# CAN.net
KiCad netlist of a schematic drawn in Altium Designer
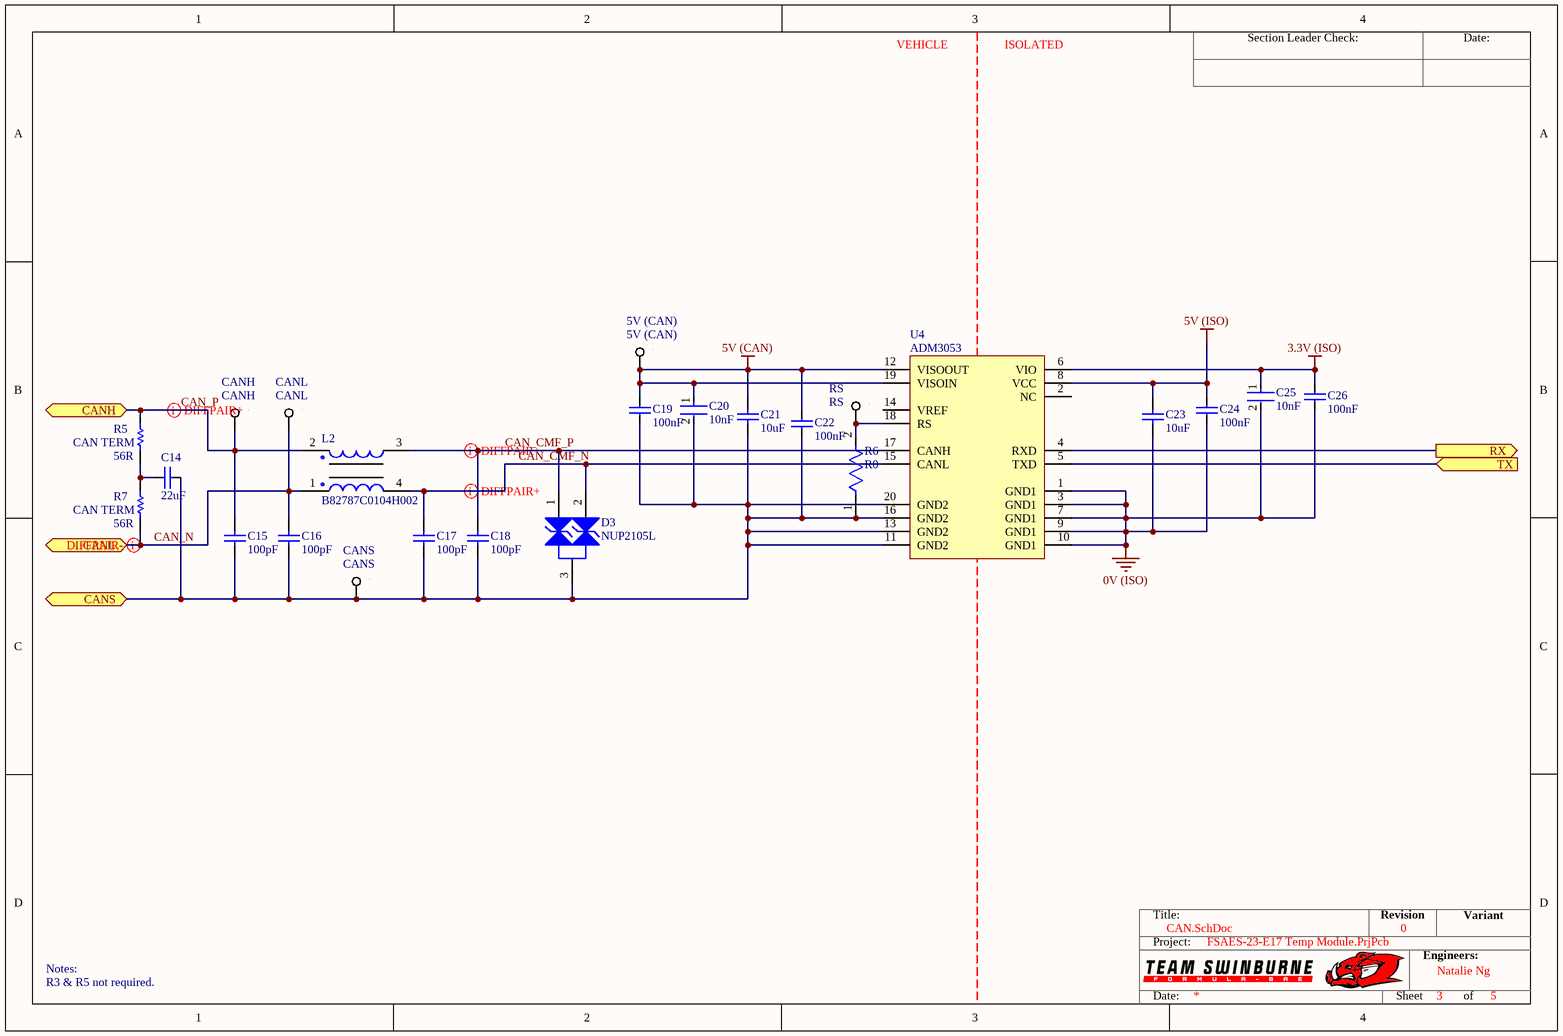
[diagram p0: CAN.SchDoc]

(export (version "E")
  (design (tool "Eeschema 10.0.6"))
  (components
    (comp (ref "5V (CAN)")
      (value "5V (CAN)")
      (footprint "SMD Test Point 1mm")
      (fields (field (name "PART NUMBER") "SMD Test Point Small") (field (name "CONTACT") "NA"))
      (libsource (lib "ts_20-standard-connectors") (part "Test Point Small"))
    )
    (comp (ref "C14")
      (value "22uF")
      (footprint "C0805C226M9PAC7210-Footprint-1")
      (description "Cap Ceramic 22uF 6.3V X5R 20% Pad SMD 0805 85C T/R")
      (fields (field (name "TOLERANCE") "20%"))
      (libsource (lib "Team Swinburne") (part "C0805C226M9PAC7210-Symbol-1"))
    )
    (comp (ref "C15")
      (value "100pF")
      (footprint "CAPC2013X70X45NL15T25")
      (description "Cap Ceramic 100pF 50V C0G 5% Pad SMD 0805 125C Automotive T/R")
      (fields (field (name "TOLERANCE") "5%"))
      (libsource (lib "Team Swinburne") (part "CAP"))
    )
    (comp (ref "C16")
      (value "100pF")
      (footprint "CAPC2013X70X45NL15T25")
      (description "Cap Ceramic 100pF 50V C0G 5% Pad SMD 0805 125C Automotive T/R")
      (fields (field (name "TOLERANCE") "5%"))
      (libsource (lib "Team Swinburne") (part "CAP"))
    )
    (comp (ref "C17")
      (value "100pF")
      (footprint "CAPC2013X70X45NL15T25")
      (description "Cap Ceramic 100pF 50V C0G 5% Pad SMD 0805 125C Automotive T/R")
      (fields (field (name "TOLERANCE") "5%"))
      (libsource (lib "Team Swinburne") (part "CAP"))
    )
    (comp (ref "C18")
      (value "100pF")
      (footprint "CAPC2013X70X45NL15T25")
      (description "Cap Ceramic 100pF 50V C0G 5% Pad SMD 0805 125C Automotive T/R")
      (fields (field (name "TOLERANCE") "5%"))
      (libsource (lib "Team Swinburne") (part "CAP"))
    )
    (comp (ref "C19")
      (value "100nF")
      (footprint "0805")
      (description "Cap Ceramic 0.1uF 25V X7R 10% Pad SMD 0805 125C Automotive T/R")
      (fields (field (name "TOLERANCE") "10%"))
      (libsource (lib "Team Swinburne") (part "Capacitors"))
    )
    (comp (ref "C20")
      (value "10nF")
      (footprint "FP-GCM319-0_15-IPC_A")
      (description "CAP CER 10000PF 100V NP0 1206")
      (fields (field (name "TOLERANCE") "5%"))
      (libsource (lib "Team Swinburne") (part "b4654b650e69147ec39a6b967a45e02"))
    )
    (comp (ref "C21")
      (value "10uF")
      (footprint "CAPC2013X145X50NL20T25")
      (description "CAP CER 10UF 10V Y5V 0805")
      (fields (field (name "TOLERANCE") "80%"))
      (libsource (lib "Team Swinburne") (part "CAP-NP-2"))
    )
    (comp (ref "C22")
      (value "100nF")
      (footprint "0805")
      (description "Cap Ceramic 0.1uF 25V X7R 10% Pad SMD 0805 125C Automotive T/R")
      (fields (field (name "TOLERANCE") "10%"))
      (libsource (lib "Team Swinburne") (part "Capacitors"))
    )
    (comp (ref "C23")
      (value "10uF")
      (footprint "CAPC2013X145X50NL20T25")
      (description "CAP CER 10UF 10V Y5V 0805")
      (fields (field (name "TOLERANCE") "80%"))
      (libsource (lib "Team Swinburne") (part "CAP-NP-2"))
    )
    (comp (ref "C24")
      (value "100nF")
      (footprint "0805")
      (description "Cap Ceramic 0.1uF 25V X7R 10% Pad SMD 0805 125C Automotive T/R")
      (fields (field (name "TOLERANCE") "10%"))
      (libsource (lib "Team Swinburne") (part "Capacitors"))
    )
    (comp (ref "C25")
      (value "10nF")
      (footprint "FP-GCM319-0_15-IPC_A")
      (description "CAP CER 10000PF 100V NP0 1206")
      (fields (field (name "TOLERANCE") "5%"))
      (libsource (lib "Team Swinburne") (part "b4654b650e69147ec39a6b967a45e02"))
    )
    (comp (ref "C26")
      (value "100nF")
      (footprint "0805")
      (description "Cap Ceramic 0.1uF 25V X7R 10% Pad SMD 0805 125C Automotive T/R")
      (fields (field (name "TOLERANCE") "10%"))
      (libsource (lib "Team Swinburne") (part "Capacitors"))
    )
    (comp (ref "CANH")
      (value "CANH")
      (footprint "SMD Test Point 1mm")
      (fields (field (name "PART NUMBER") "SMD Test Point Small") (field (name "CONTACT") "NA"))
      (libsource (lib "ts_20-standard-connectors") (part "Test Point Small"))
    )
    (comp (ref "CANL")
      (value "CANL")
      (footprint "SMD Test Point 1mm")
      (fields (field (name "PART NUMBER") "SMD Test Point Small") (field (name "CONTACT") "NA"))
      (libsource (lib "ts_20-standard-connectors") (part "Test Point Small"))
    )
    (comp (ref "CANS")
      (value "CANS")
      (footprint "SMD Test Point 1mm")
      (fields (field (name "PART NUMBER") "SMD Test Point Small") (field (name "CONTACT") "NA"))
      (libsource (lib "ts_20-standard-connectors") (part "Test Point Small"))
    )
    (comp (ref "D3")
      (value "NUP2105L")
      (footprint "ONSC-SOT-23-3-318-08_V")
      (description "NUP2105L Series 350 W Dual Line CAN Bus Protector ESD Protection Diode - SOT-23")
      (libsource (lib "Team Swinburne") (part "ONSC-NUP21X5X-SOT-23-3-318-08"))
    )
    (comp (ref "L2")
      (value "B82787C0104H002")
      (footprint "TDK 4-PC Pad")
      (description "100µH @ 100kHz 2 Line Common Mode Choke Surface Mount 5.8 kOhms @ 10MHz 150mA DCR 2Ohm")
      (fields
        (field (name "MANUFACTURER") "EPCOS (TDK)")
        (field (name "DIGIKEY PART NUMBER") "495-4598-1-ND")
      )
      (libsource (lib "ts_20-standard-library") (part "B82787C0104H002"))
    )
    (comp (ref "R5")
      (value "CAN TERM")
      (footprint "RESC0603")
      (description "RES SMD 56 OHM JUMPER 1/10W 0603")
      (fields (field (name "ALTIUM_VALUE") "56R") (field (name "TOLERANCE") "1%"))
      (libsource (lib "Team Swinburne") (part "Resistor"))
    )
    (comp (ref "R6")
      (value "R0")
      (footprint "FP-RC0805-IPC_A")
      (description "Res Thick Film 0805 0 Ohm Epoxy Pad SMD T/R")
      (fields (field (name "TOLERANCE") "1%"))
      (libsource (lib "Team Swinburne") (part "1029c3af85768c4190bb7ad29bc67b5"))
    )
    (comp (ref "R7")
      (value "CAN TERM")
      (footprint "RESC0603")
      (description "RES SMD 56 OHM JUMPER 1/10W 0603")
      (fields (field (name "ALTIUM_VALUE") "56R") (field (name "TOLERANCE") "1%"))
      (libsource (lib "Team Swinburne") (part "Resistor"))
    )
    (comp (ref "RS")
      (value "RS")
      (footprint "SMD Test Point 1mm")
      (fields (field (name "PART NUMBER") "SMD Test Point Small") (field (name "CONTACT") "NA"))
      (libsource (lib "ts_20-standard-connectors") (part "Test Point Small"))
    )
    (comp (ref "U4")
      (value "ADM3053")
      (footprint "AD SOIC-W 20")
      (description "Isolated CAN Transceiver")
      (fields
        (field (name "MANUFACTURER") "Analogue Devices")
        (field (name "DIGIKEY PART NUMBER") "ADM3053BRWZ-ND")
      )
      (libsource (lib "ts_20-standard-library") (part "ADM3053"))
    )
  )
  (nets
    (net (code "1") (name "/CANS") (class "Default")
      (node (ref "C14") (pin "2") (pinfunction "2_2") (pintype "passive"))
      (node (ref "C15") (pin "1") (pinfunction "1_1") (pintype "passive"))
      (node (ref "C16") (pin "1") (pinfunction "1_1") (pintype "passive"))
      (node (ref "C17") (pin "1") (pinfunction "1_1") (pintype "passive"))
      (node (ref "C18") (pin "1") (pinfunction "1_1") (pintype "passive"))
      (node (ref "C19") (pin "2") (pinfunction "2_2") (pintype "passive"))
      (node (ref "C20") (pin "2") (pinfunction "2_2") (pintype "passive"))
      (node (ref "C21") (pin "1") (pinfunction "1_1") (pintype "passive"))
      (node (ref "C22") (pin "2") (pinfunction "2_2") (pintype "passive"))
      (node (ref "CANS") (pin "1") (pinfunction "1_1") (pintype "passive"))
      (node (ref "D3") (pin "3") (pinfunction "K_3") (pintype "passive"))
      (node (ref "R6") (pin "1") (pinfunction "1_1") (pintype "passive"))
      (node (ref "U4") (pin "11") (pinfunction "GND2_11") (pintype "passive"))
      (node (ref "U4") (pin "13") (pinfunction "GND2_13") (pintype "passive"))
      (node (ref "U4") (pin "16") (pinfunction "GND2_16") (pintype "passive"))
      (node (ref "U4") (pin "20") (pinfunction "GND2_20") (pintype "passive"))
    )
    (net (code "2") (name "/CAN_CMF_N") (class "Default")
      (node (ref "C17") (pin "2") (pinfunction "2_2") (pintype "passive"))
      (node (ref "D3") (pin "2") (pinfunction "K_2") (pintype "passive"))
      (node (ref "L2") (pin "4") (pinfunction "4_4") (pintype "passive"))
      (node (ref "U4") (pin "15") (pinfunction "CANL_15") (pintype "passive"))
    )
    (net (code "3") (name "/CAN_CMF_P") (class "Default")
      (node (ref "C18") (pin "2") (pinfunction "2_2") (pintype "passive"))
      (node (ref "D3") (pin "1") (pinfunction "K_1") (pintype "passive"))
      (node (ref "L2") (pin "3") (pinfunction "3_3") (pintype "power_in"))
      (node (ref "U4") (pin "17") (pinfunction "CANH_17") (pintype "passive"))
    )
    (net (code "4") (name "/CAN_N") (class "Default")
      (node (ref "C16") (pin "2") (pinfunction "2_2") (pintype "passive"))
      (node (ref "CANL") (pin "1") (pinfunction "1_1") (pintype "passive"))
      (node (ref "L2") (pin "1") (pinfunction "1_1") (pintype "passive"))
      (node (ref "R7") (pin "1") (pinfunction "1_1") (pintype "passive"))
    )
    (net (code "5") (name "/CAN_P") (class "Default")
      (node (ref "C15") (pin "2") (pinfunction "2_2") (pintype "passive"))
      (node (ref "CANH") (pin "1") (pinfunction "1_1") (pintype "passive"))
      (node (ref "L2") (pin "2") (pinfunction "2_2") (pintype "passive"))
      (node (ref "R5") (pin "2") (pinfunction "2_2") (pintype "passive"))
    )
    (net (code "6") (name "/RX") (class "Default")
      (node (ref "U4") (pin "4") (pinfunction "RXD_4") (pintype "passive"))
    )
    (net (code "7") (name "/TX") (class "Default")
      (node (ref "U4") (pin "5") (pinfunction "TXD_5") (pintype "passive"))
    )
    (net (code "8") (name "0V (ISO)") (class "Default")
      (node (ref "C23") (pin "1") (pinfunction "1_1") (pintype "passive"))
      (node (ref "C24") (pin "2") (pinfunction "2_2") (pintype "passive"))
      (node (ref "C25") (pin "2") (pinfunction "2_2") (pintype "passive"))
      (node (ref "C26") (pin "2") (pinfunction "2_2") (pintype "passive"))
      (node (ref "U4") (pin "1") (pinfunction "GND1_1") (pintype "passive"))
      (node (ref "U4") (pin "10") (pinfunction "GND1_10") (pintype "passive"))
      (node (ref "U4") (pin "3") (pinfunction "GND1_3") (pintype "passive"))
      (node (ref "U4") (pin "7") (pinfunction "GND1_7") (pintype "passive"))
      (node (ref "U4") (pin "9") (pinfunction "GND1_9") (pintype "passive"))
    )
    (net (code "9") (name "3.3V (ISO)") (class "Default")
      (node (ref "C25") (pin "1") (pinfunction "1_1") (pintype "passive"))
      (node (ref "C26") (pin "1") (pinfunction "1_1") (pintype "passive"))
      (node (ref "U4") (pin "6") (pinfunction "VIO_6") (pintype "passive"))
    )
    (net (code "10") (name "5V (CAN)") (class "Default")
      (node (ref "5V (CAN)") (pin "1") (pinfunction "1_1") (pintype "passive"))
      (node (ref "C19") (pin "1") (pinfunction "1_1") (pintype "passive"))
      (node (ref "C20") (pin "1") (pinfunction "1_1") (pintype "passive"))
      (node (ref "C21") (pin "2") (pinfunction "2_2") (pintype "passive"))
      (node (ref "C22") (pin "1") (pinfunction "1_1") (pintype "passive"))
      (node (ref "U4") (pin "12") (pinfunction "VISOOUT_12") (pintype "passive"))
      (node (ref "U4") (pin "19") (pinfunction "VISOIN_19") (pintype "passive"))
    )
    (net (code "11") (name "5V (ISO)") (class "Default")
      (node (ref "C23") (pin "2") (pinfunction "2_2") (pintype "passive"))
      (node (ref "C24") (pin "1") (pinfunction "1_1") (pintype "passive"))
      (node (ref "U4") (pin "8") (pinfunction "VCC_8") (pintype "passive"))
    )
    (net (code "12") (name "Net-(C14-Pad1)") (class "Default")
      (node (ref "C14") (pin "1") (pinfunction "1_1") (pintype "passive"))
      (node (ref "R5") (pin "1") (pinfunction "1_1") (pintype "passive"))
      (node (ref "R7") (pin "2") (pinfunction "2_2") (pintype "passive"))
    )
    (net (code "13") (name "Net-(U4-RS)") (class "Default")
      (node (ref "R6") (pin "2") (pinfunction "2_2") (pintype "passive"))
      (node (ref "RS") (pin "1") (pinfunction "1_1") (pintype "passive"))
      (node (ref "U4") (pin "18") (pinfunction "RS_18") (pintype "passive"))
    )
    (net (code "14") (name "unconnected-(U4-NC-Pad2)") (class "Default")
      (node (ref "U4") (pin "2") (pinfunction "NC_2") (pintype "passive"))
    )
    (net (code "15") (name "unconnected-(U4-VREF-Pad14)") (class "Default")
      (node (ref "U4") (pin "14") (pinfunction "VREF_14") (pintype "passive"))
    )
  )
)
